# Dehyrator_TV01.net
KiCad netlist of a schematic drawn in Altium Designer
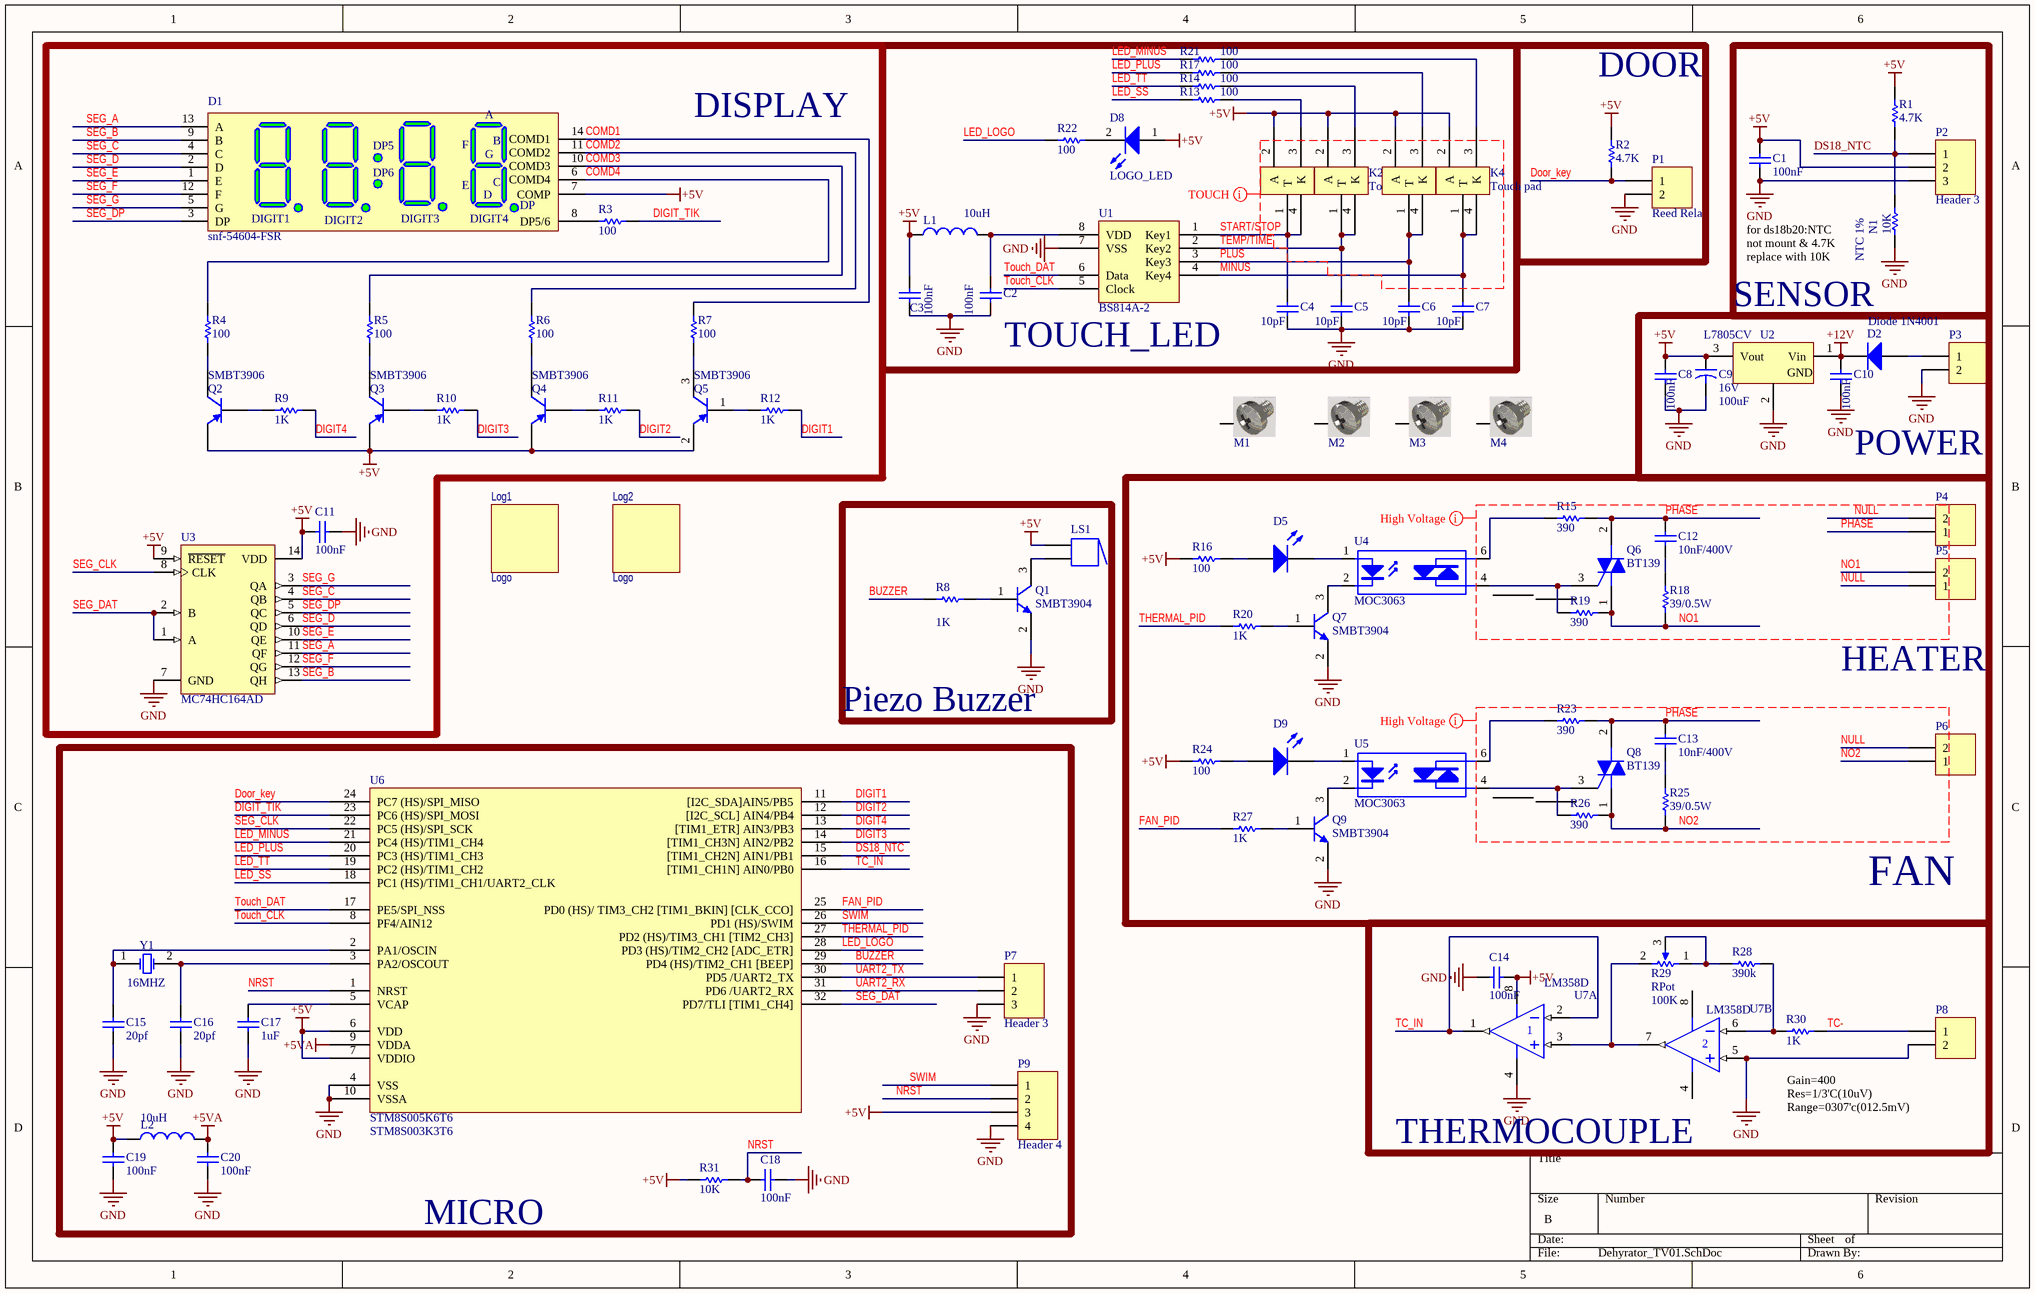
[diagram p0: Dehyrator_TV01.SchDoc]

(export (version "E")
  (design (tool "Eeschema 10.0.6"))
  (components
    (comp (ref "C1")
      (value "100nF")
      (footprint "CAP0805")
      (description "Capacitor")
      (fields (field (name "Comment") "Cap") (field (name "PUBLISHER") "Altium Limited"))
      (libsource (lib "Miscellaneous Devices") (part "Cap"))
    )
    (comp (ref "C2")
      (value "100nF")
      (footprint "CAP0805")
      (description "Capacitor")
      (fields (field (name "Comment") "Cap") (field (name "PUBLISHER") "Altium Limited"))
      (libsource (lib "Miscellaneous Devices") (part "Cap"))
    )
    (comp (ref "C3")
      (value "100nF")
      (footprint "CAP0805")
      (description "Capacitor")
      (fields (field (name "Comment") "Cap") (field (name "PUBLISHER") "Altium Limited"))
      (libsource (lib "Miscellaneous Devices") (part "Cap"))
    )
    (comp (ref "C4")
      (value "10pF")
      (footprint "CAP0805")
      (description "Capacitor")
      (fields (field (name "Comment") "Cap") (field (name "PUBLISHER") "Altium Limited"))
      (libsource (lib "Miscellaneous Devices") (part "Cap"))
    )
    (comp (ref "C5")
      (value "10pF")
      (footprint "CAP0805")
      (description "Capacitor")
      (fields (field (name "Comment") "Cap") (field (name "PUBLISHER") "Altium Limited"))
      (libsource (lib "Miscellaneous Devices") (part "Cap"))
    )
    (comp (ref "C6")
      (value "10pF")
      (footprint "CAP0805")
      (description "Capacitor")
      (fields (field (name "Comment") "Cap") (field (name "PUBLISHER") "Altium Limited"))
      (libsource (lib "Miscellaneous Devices") (part "Cap"))
    )
    (comp (ref "C7")
      (value "10pF")
      (footprint "CAP0805")
      (description "Capacitor")
      (fields (field (name "Comment") "Cap") (field (name "PUBLISHER") "Altium Limited"))
      (libsource (lib "Miscellaneous Devices") (part "Cap"))
    )
    (comp (ref "C8")
      (value "100nF")
      (footprint "CAP0805")
      (description "Capacitor")
      (fields (field (name "Comment") "Cap") (field (name "PUBLISHER") "Altium Limited"))
      (libsource (lib "Miscellaneous Devices") (part "Cap"))
    )
    (comp (ref "C9")
      (value "16V")
      (footprint "Cap electrolitic radial 5x11-2")
      (description "Capacitor")
      (fields (field (name "ALTIUM_VALUE") "100uF") (field (name "PUBLISHER") "Altium Limited"))
      (libsource (lib "Miscellaneous Devices") (part "Cap2"))
    )
    (comp (ref "C10")
      (value "100nF")
      (footprint "CAP0805")
      (description "Capacitor")
      (fields (field (name "Comment") "Cap") (field (name "PUBLISHER") "Altium Limited"))
      (libsource (lib "Miscellaneous Devices") (part "Cap"))
    )
    (comp (ref "C11")
      (value "100nF")
      (footprint "CAP0805")
      (description "Capacitor")
      (fields (field (name "Comment") "Cap") (field (name "PUBLISHER") "Altium Limited"))
      (libsource (lib "Miscellaneous Devices") (part "Cap"))
    )
    (comp (ref "C12")
      (value "10nF/400V")
      (footprint "Cap_polyester_400V")
      (description "Capacitor")
      (fields (field (name "PUBLISHER") "Altium Limited"))
      (libsource (lib "Miscellaneous Devices") (part "Cap"))
    )
    (comp (ref "C13")
      (value "10nF/400V")
      (footprint "Cap_polyester_400V")
      (description "Capacitor")
      (fields (field (name "PUBLISHER") "Altium Limited"))
      (libsource (lib "Miscellaneous Devices") (part "Cap"))
    )
    (comp (ref "C14")
      (value "100nF")
      (footprint "CAP0805")
      (description "Capacitor")
      (fields (field (name "Comment") "Cap") (field (name "PUBLISHER") "Altium Limited"))
      (libsource (lib "Miscellaneous Devices") (part "Cap"))
    )
    (comp (ref "C15")
      (value "20pf")
      (footprint "CAP0805")
      (description "Capacitor")
      (fields (field (name "Comment") "Cap") (field (name "PUBLISHER") "Altium Limited"))
      (libsource (lib "Miscellaneous Devices") (part "Cap"))
    )
    (comp (ref "C16")
      (value "20pf")
      (footprint "CAP0805")
      (description "Capacitor")
      (fields (field (name "Comment") "Cap") (field (name "PUBLISHER") "Altium Limited"))
      (libsource (lib "Miscellaneous Devices") (part "Cap"))
    )
    (comp (ref "C17")
      (value "1uF")
      (footprint "CAP0805")
      (description "Capacitor")
      (fields (field (name "Comment") "Cap") (field (name "PUBLISHER") "Altium Limited"))
      (libsource (lib "Miscellaneous Devices") (part "Cap"))
    )
    (comp (ref "C18")
      (value "100nF")
      (footprint "CAP0805")
      (description "Capacitor")
      (fields (field (name "Comment") "Cap") (field (name "PUBLISHER") "Altium Limited"))
      (libsource (lib "Miscellaneous Devices") (part "Cap"))
    )
    (comp (ref "C19")
      (value "100nF")
      (footprint "CAP0805")
      (description "Capacitor")
      (fields (field (name "Comment") "Cap") (field (name "PUBLISHER") "Altium Limited"))
      (libsource (lib "Miscellaneous Devices") (part "Cap"))
    )
    (comp (ref "C20")
      (value "100nF")
      (footprint "CAP0805")
      (description "Capacitor")
      (fields (field (name "Comment") "Cap") (field (name "PUBLISHER") "Altium Limited"))
      (libsource (lib "Miscellaneous Devices") (part "Cap"))
    )
    (comp (ref "D1")
      (value "snf-54604-FSR")
      (footprint "7SEG-4CLOCK-50x19")
      (description "4-Digit LED Display CLOCK")
      (libsource (lib "Mofidi3D") (part "7SEG-CLOCK-14PIN"))
    )
    (comp (ref "D2")
      (value "Diode 1N4001")
      (footprint "DO-241AC")
      (description "1 Amp General Purpose Rectifier")
      (fields (field (name "PUBLISHER") "Altium Limited"))
      (libsource (lib "Miscellaneous Devices") (part "Diode 1N4001"))
    )
    (comp (ref "D5")
      (value "LED1")
      (footprint "LED_0805")
      (description "Typical RED GaAs LED")
      (fields (field (name "PUBLISHER") "Altium Limited"))
      (libsource (lib "Miscellaneous Devices") (part "LED1"))
    )
    (comp (ref "D8")
      (value "LOGO_LED")
      (footprint "LED5MM_BLUE")
      (description "Typical INFRARED GaAs LED")
      (fields (field (name "PUBLISHER") "Altium Limited"))
      (libsource (lib "Miscellaneous Devices") (part "LED0"))
    )
    (comp (ref "D9")
      (value "LED1")
      (footprint "LED_0805")
      (description "Typical RED GaAs LED")
      (fields (field (name "PUBLISHER") "Altium Limited"))
      (libsource (lib "Miscellaneous Devices") (part "LED1"))
    )
    (comp (ref "K1")
      (value "Touch pad")
      (footprint "Touchled_Circular")
      (description "Capacitive touch")
      (libsource (lib "Mofidi3D") (part "Touch_Pad"))
    )
    (comp (ref "K2")
      (value "Touch pad")
      (footprint "Touchled_Circular")
      (description "Capacitive touch")
      (libsource (lib "Mofidi3D") (part "Touch_Pad"))
    )
    (comp (ref "K3")
      (value "Touch pad")
      (footprint "Touchled_Circular")
      (description "Capacitive touch")
      (libsource (lib "Mofidi3D") (part "Touch_Pad"))
    )
    (comp (ref "K4")
      (value "Touch pad")
      (footprint "Touchled_Circular")
      (description "Capacitive touch")
      (libsource (lib "Mofidi3D") (part "Touch_Pad"))
    )
    (comp (ref "L1")
      (value "10uH")
      (footprint "IND0805")
      (description "Inductor")
      (fields (field (name "PUBLISHER") "Altium Limited"))
      (libsource (lib "Miscellaneous Devices") (part "Inductor"))
    )
    (comp (ref "L2")
      (value "10uH")
      (footprint "IND0805")
      (description "Inductor")
      (fields (field (name "PUBLISHER") "Altium Limited"))
      (libsource (lib "Miscellaneous Devices") (part "Inductor"))
    )
    (comp (ref "Log1") (value "Logo") (footprint "LOGO_PARS_TOP") (libsource (lib "Mofidi3D") (part "Logo")))
    (comp (ref "Log2") (value "Logo") (footprint "LOGO_PARS_TOP") (libsource (lib "Mofidi3D") (part "Logo")))
    (comp (ref "LS1")
      (value "Buzzer")
      (footprint "BUZZER_12A05")
      (description "Magnetic Transducer Buzzer")
      (fields (field (name "PUBLISHER") "Altium Limited"))
      (libsource (lib "Miscellaneous Devices") (part "Buzzer"))
    )
    (comp (ref "M1")
      (value "Screw3mm")
      (footprint "Board Screw 3mm")
      (description "Board Screw With Spacer 3mm")
      (fields (field (name "DESIGNER") "Abbas Basereh"))
      (libsource (lib "Mofidi3D") (part "Board Screw 3mm"))
    )
    (comp (ref "M2")
      (value "Screw3mm")
      (footprint "Board Screw 3mm")
      (description "Board Screw With Spacer 3mm")
      (fields (field (name "DESIGNER") "Abbas Basereh"))
      (libsource (lib "Mofidi3D") (part "Board Screw 3mm"))
    )
    (comp (ref "M3")
      (value "Screw3mm")
      (footprint "Board Screw 3mm")
      (description "Board Screw With Spacer 3mm")
      (fields (field (name "DESIGNER") "Abbas Basereh"))
      (libsource (lib "Mofidi3D") (part "Board Screw 3mm"))
    )
    (comp (ref "M4")
      (value "Screw3mm")
      (footprint "Board Screw 3mm")
      (description "Board Screw With Spacer 3mm")
      (fields (field (name "DESIGNER") "Abbas Basereh"))
      (libsource (lib "Mofidi3D") (part "Board Screw 3mm"))
    )
    (comp (ref "N1")
      (value "NTC 1%")
      (footprint "Axial 0_25 W, 0_4 IN LEAD PITCH")
      (description "Resistor")
      (fields (field (name "ALTIUM_VALUE") "10K") (field (name "PUBLISHER") "Altium Limited"))
      (libsource (lib "Miscellaneous Devices") (part "Res1"))
    )
    (comp (ref "P1")
      (value "Reed Relay")
      (footprint "DS1070-2-COMCON")
      (description "Header, 2-Pin")
      (fields (field (name "PUBLISHER") "Altium Limited"))
      (libsource (lib "Miscellaneous Connectors") (part "Header 2"))
    )
    (comp (ref "P2")
      (value "Header 3")
      (footprint "XH-3PIN")
      (description "Header, 3-Pin")
      (fields (field (name "PUBLISHER") "Altium Limited"))
      (libsource (lib "Miscellaneous Connectors") (part "Header 3"))
    )
    (comp (ref "P3")
      (value "Header 2")
      (footprint "KF301 2PIN")
      (description "Header, 2-Pin")
      (fields (field (name "PUBLISHER") "Altium Limited"))
      (libsource (lib "Miscellaneous Connectors") (part "Header 2"))
    )
    (comp (ref "P4")
      (value "Header 2")
      (footprint "KF301 2PIN")
      (description "Header, 2-Pin")
      (fields (field (name "PUBLISHER") "Altium Limited"))
      (libsource (lib "") (part "Header 2_1"))
    )
    (comp (ref "P5")
      (value "Header 2")
      (footprint "KF301 2PIN")
      (description "Header, 2-Pin")
      (fields (field (name "PUBLISHER") "Altium Limited"))
      (libsource (lib "") (part "Header 2_1"))
    )
    (comp (ref "P6")
      (value "Header 2")
      (footprint "KF301 2PIN")
      (description "Header, 2-Pin")
      (fields (field (name "PUBLISHER") "Altium Limited"))
      (libsource (lib "") (part "Header 2_1"))
    )
    (comp (ref "P7")
      (value "Header 3")
      (footprint "PIN_M_1x3")
      (description "Header, 3-Pin")
      (fields (field (name "PUBLISHER") "Altium Limited"))
      (libsource (lib "Miscellaneous Connectors") (part "Header 3"))
    )
    (comp (ref "P8")
      (value "Header 2")
      (footprint "KF35C 2PIN")
      (description "Header, 2-Pin")
      (fields (field (name "PUBLISHER") "Altium Limited"))
      (libsource (lib "Miscellaneous Connectors") (part "Header 2"))
    )
    (comp (ref "P9")
      (value "Header 4")
      (footprint "HDR_1x4")
      (description "Header, 4-Pin")
      (fields (field (name "PUBLISHER") "Altium Limited"))
      (libsource (lib "Miscellaneous Connectors") (part "Header 4"))
    )
    (comp (ref "Q1")
      (value "SMBT3904")
      (footprint "SOT23_N")
      (description "NPN Silicon Switching Transistor, 40 V VCEO, 200 mA IC, SOT23, Reel, Green")
      (fields (field (name "MANUFACTURER") "Infineon"))
      (libsource (lib "Infineon Transistor & Diode") (part "SMBT3904"))
    )
    (comp (ref "Q2")
      (value "SMBT3906")
      (footprint "SOT23_N")
      (description "PNP Silicon Switching Transistor, 40 V VCEO, 200 mA IC, SOT23, Reel, Green")
      (fields (field (name "MANUFACTURER") "Infineon"))
      (libsource (lib "Infineon Transistor & Diode") (part "SMBT3906"))
    )
    (comp (ref "Q3")
      (value "SMBT3906")
      (footprint "SOT23_N")
      (description "PNP Silicon Switching Transistor, 40 V VCEO, 200 mA IC, SOT23, Reel, Green")
      (fields (field (name "MANUFACTURER") "Infineon"))
      (libsource (lib "Infineon Transistor & Diode") (part "SMBT3906"))
    )
    (comp (ref "Q4")
      (value "SMBT3906")
      (footprint "SOT23_N")
      (description "PNP Silicon Switching Transistor, 40 V VCEO, 200 mA IC, SOT23, Reel, Green")
      (fields (field (name "MANUFACTURER") "Infineon"))
      (libsource (lib "Infineon Transistor & Diode") (part "SMBT3906"))
    )
    (comp (ref "Q5")
      (value "SMBT3906")
      (footprint "SOT23_N")
      (description "PNP Silicon Switching Transistor, 40 V VCEO, 200 mA IC, SOT23, Reel, Green")
      (fields (field (name "MANUFACTURER") "Infineon"))
      (libsource (lib "") (part "SMBT3906_1"))
    )
    (comp (ref "Q6")
      (value "BT139")
      (footprint "TO-220 AB WITH HEAT SINK")
      (description "Silicon Bidirectional Triode Thyristor")
      (fields (field (name "PUBLISHER") "Altium Limited"))
      (libsource (lib "Miscellaneous Devices") (part "Triac"))
    )
    (comp (ref "Q7")
      (value "SMBT3904")
      (footprint "SOT23_N")
      (description "NPN Silicon Switching Transistor, 40 V VCEO, 200 mA IC, SOT23, Reel, Green")
      (fields (field (name "MANUFACTURER") "Infineon"))
      (libsource (lib "Infineon Transistor & Diode") (part "SMBT3904"))
    )
    (comp (ref "Q8")
      (value "BT139")
      (footprint "TO-220 AB WITH HEAT SINK")
      (description "Silicon Bidirectional Triode Thyristor")
      (fields (field (name "PUBLISHER") "Altium Limited"))
      (libsource (lib "Miscellaneous Devices") (part "Triac"))
    )
    (comp (ref "Q9")
      (value "SMBT3904")
      (footprint "SOT23_N")
      (description "NPN Silicon Switching Transistor, 40 V VCEO, 200 mA IC, SOT23, Reel, Green")
      (fields (field (name "MANUFACTURER") "Infineon"))
      (libsource (lib "Infineon Transistor & Diode") (part "SMBT3904"))
    )
    (comp (ref "R1")
      (value "4.7K")
      (footprint "RES0805")
      (description "Resistor")
      (fields (field (name "Comment") "Res1") (field (name "PUBLISHER") "Altium Limited"))
      (libsource (lib "Miscellaneous Devices") (part "Res1"))
    )
    (comp (ref "R2")
      (value "4.7K")
      (footprint "RES0805")
      (description "Resistor")
      (fields (field (name "Comment") "Res1") (field (name "PUBLISHER") "Altium Limited"))
      (libsource (lib "Miscellaneous Devices") (part "Res1"))
    )
    (comp (ref "R3")
      (value "100")
      (footprint "RES0805")
      (description "Resistor")
      (fields (field (name "Comment") "Res1") (field (name "PUBLISHER") "Altium Limited"))
      (libsource (lib "Miscellaneous Devices") (part "Res1"))
    )
    (comp (ref "R4")
      (value "100")
      (footprint "RES0805")
      (description "Resistor")
      (fields (field (name "Comment") "Res1") (field (name "PUBLISHER") "Altium Limited"))
      (libsource (lib "Miscellaneous Devices") (part "Res1"))
    )
    (comp (ref "R5")
      (value "100")
      (footprint "RES0805")
      (description "Resistor")
      (fields (field (name "Comment") "Res1") (field (name "PUBLISHER") "Altium Limited"))
      (libsource (lib "Miscellaneous Devices") (part "Res1"))
    )
    (comp (ref "R6")
      (value "100")
      (footprint "RES0805")
      (description "Resistor")
      (fields (field (name "Comment") "Res1") (field (name "PUBLISHER") "Altium Limited"))
      (libsource (lib "Miscellaneous Devices") (part "Res1"))
    )
    (comp (ref "R7")
      (value "100")
      (footprint "RES0805")
      (description "Resistor")
      (fields (field (name "Comment") "Res1") (field (name "PUBLISHER") "Altium Limited"))
      (libsource (lib "Miscellaneous Devices") (part "Res1"))
    )
    (comp (ref "R8")
      (value "1K")
      (footprint "RES0805")
      (description "Resistor")
      (fields (field (name "Comment") "Res1") (field (name "PUBLISHER") "Altium Limited"))
      (libsource (lib "Miscellaneous Devices") (part "Res1"))
    )
    (comp (ref "R9")
      (value "1K")
      (footprint "RES0805")
      (description "Resistor")
      (fields (field (name "Comment") "Res1") (field (name "PUBLISHER") "Altium Limited"))
      (libsource (lib "Miscellaneous Devices") (part "Res1"))
    )
    (comp (ref "R10")
      (value "1K")
      (footprint "RES0805")
      (description "Resistor")
      (fields (field (name "Comment") "Res1") (field (name "PUBLISHER") "Altium Limited"))
      (libsource (lib "Miscellaneous Devices") (part "Res1"))
    )
    (comp (ref "R11")
      (value "1K")
      (footprint "RES0805")
      (description "Resistor")
      (fields (field (name "Comment") "Res1") (field (name "PUBLISHER") "Altium Limited"))
      (libsource (lib "Miscellaneous Devices") (part "Res1"))
    )
    (comp (ref "R12")
      (value "1K")
      (footprint "RES0805")
      (description "Resistor")
      (fields (field (name "Comment") "Res1") (field (name "PUBLISHER") "Altium Limited"))
      (libsource (lib "Miscellaneous Devices") (part "Res1"))
    )
    (comp (ref "R13")
      (value "100")
      (footprint "RES0805")
      (description "Resistor")
      (fields (field (name "Comment") "Res1") (field (name "PUBLISHER") "Altium Limited"))
      (libsource (lib "Miscellaneous Devices") (part "Res1"))
    )
    (comp (ref "R14")
      (value "100")
      (footprint "RES0805")
      (description "Resistor")
      (fields (field (name "Comment") "Res1") (field (name "PUBLISHER") "Altium Limited"))
      (libsource (lib "Miscellaneous Devices") (part "Res1"))
    )
    (comp (ref "R15")
      (value "390")
      (footprint "Axial 0_5W 5_0mm")
      (description "Resistor")
      (fields (field (name "Comment") "Res1") (field (name "PUBLISHER") "Altium Limited"))
      (libsource (lib "Miscellaneous Devices") (part "Res1"))
    )
    (comp (ref "R16")
      (value "100")
      (footprint "RES0805")
      (description "Resistor")
      (fields (field (name "Comment") "Res1") (field (name "PUBLISHER") "Altium Limited"))
      (libsource (lib "Miscellaneous Devices") (part "Res1"))
    )
    (comp (ref "R17")
      (value "100")
      (footprint "RES0805")
      (description "Resistor")
      (fields (field (name "Comment") "Res1") (field (name "PUBLISHER") "Altium Limited"))
      (libsource (lib "Miscellaneous Devices") (part "Res1"))
    )
    (comp (ref "R18")
      (value "39/0.5W")
      (footprint "Axial 1W  7_0mm")
      (description "Resistor")
      (fields (field (name "Comment") "Res1") (field (name "PUBLISHER") "Altium Limited"))
      (libsource (lib "Miscellaneous Devices") (part "Res1"))
    )
    (comp (ref "R19")
      (value "390")
      (footprint "Axial 0_5W 5_0mm")
      (description "Resistor")
      (fields (field (name "Comment") "Res1") (field (name "PUBLISHER") "Altium Limited"))
      (libsource (lib "Miscellaneous Devices") (part "Res1"))
    )
    (comp (ref "R20")
      (value "1K")
      (footprint "RES0805")
      (description "Resistor")
      (fields (field (name "Comment") "Res1") (field (name "PUBLISHER") "Altium Limited"))
      (libsource (lib "Miscellaneous Devices") (part "Res1"))
    )
    (comp (ref "R21")
      (value "100")
      (footprint "RES0805")
      (description "Resistor")
      (fields (field (name "Comment") "Res1") (field (name "PUBLISHER") "Altium Limited"))
      (libsource (lib "Miscellaneous Devices") (part "Res1"))
    )
    (comp (ref "R22")
      (value "100")
      (footprint "RES0805")
      (description "Resistor")
      (fields (field (name "Comment") "Res1") (field (name "PUBLISHER") "Altium Limited"))
      (libsource (lib "Miscellaneous Devices") (part "Res1"))
    )
    (comp (ref "R23")
      (value "390")
      (footprint "Axial 0_5W 5_0mm")
      (description "Resistor")
      (fields (field (name "Comment") "Res1") (field (name "PUBLISHER") "Altium Limited"))
      (libsource (lib "Miscellaneous Devices") (part "Res1"))
    )
    (comp (ref "R24")
      (value "100")
      (footprint "RES0805")
      (description "Resistor")
      (fields (field (name "Comment") "Res1") (field (name "PUBLISHER") "Altium Limited"))
      (libsource (lib "Miscellaneous Devices") (part "Res1"))
    )
    (comp (ref "R25")
      (value "39/0.5W")
      (footprint "Axial 1W  7_0mm")
      (description "Resistor")
      (fields (field (name "Comment") "Res1") (field (name "PUBLISHER") "Altium Limited"))
      (libsource (lib "Miscellaneous Devices") (part "Res1"))
    )
    (comp (ref "R26")
      (value "390")
      (footprint "Axial 0_5W 5_0mm")
      (description "Resistor")
      (fields (field (name "Comment") "Res1") (field (name "PUBLISHER") "Altium Limited"))
      (libsource (lib "Miscellaneous Devices") (part "Res1"))
    )
    (comp (ref "R27")
      (value "1K")
      (footprint "RES0805")
      (description "Resistor")
      (fields (field (name "Comment") "Res1") (field (name "PUBLISHER") "Altium Limited"))
      (libsource (lib "Miscellaneous Devices") (part "Res1"))
    )
    (comp (ref "R28")
      (value "390k")
      (footprint "RES0805")
      (description "Resistor")
      (fields (field (name "Comment") "Res1") (field (name "PUBLISHER") "Altium Limited"))
      (libsource (lib "Miscellaneous Devices") (part "Res1"))
    )
    (comp (ref "R29")
      (value "RPot")
      (footprint "Potentiometer_4mm_3364A_smd")
      (description "Potentiometer")
      (fields (field (name "ALTIUM_VALUE") "100K") (field (name "PUBLISHER") "Altium Limited"))
      (libsource (lib "Miscellaneous Devices") (part "RPot"))
    )
    (comp (ref "R30")
      (value "1K")
      (footprint "RES0805")
      (description "Resistor")
      (fields (field (name "Comment") "Res1") (field (name "PUBLISHER") "Altium Limited"))
      (libsource (lib "Miscellaneous Devices") (part "Res1"))
    )
    (comp (ref "R31")
      (value "10K")
      (footprint "RES0805")
      (description "Resistor")
      (fields (field (name "Comment") "Res1") (field (name "PUBLISHER") "Altium Limited"))
      (libsource (lib "Miscellaneous Devices") (part "Res1"))
    )
    (comp (ref "U1")
      (value "BS814A-2")
      (footprint "SO-8N")
      (description "Holtek Touch Key")
      (libsource (lib "Mofidi3D") (part "BS814A-2"))
    )
    (comp (ref "U2")
      (value "L7805CV")
      (footprint "TO-220 AB WITH HEAT SINK")
      (description "Linear Voltage Regulator IC Positive FIXED")
      (fields (field (name "MANUFACTURER") "STMicroelectronics") (field (name "DESIGNER") "Abbas Basereh"))
      (libsource (lib "Mofidi3D") (part "L7805CV-Linear Voltage Regulator IC Positive 1 Output 5V 1.5A TO-220AB"))
    )
    (comp (ref "U3")
      (value "MC74HC164AD")
      (footprint "SO14_N")
      (description "8-Bit Serial Input / Parallel-Output Shift Register")
      (fields (field (name "PUBLISHER") "Altium Limited"))
      (libsource (lib "ON Semi Logic Register") (part "MC74HC164AD"))
    )
    (comp (ref "U4")
      (value "MOC3063")
      (footprint "MOC3063")
      (description "Opto-Triac")
      (fields (field (name "PUBLISHER") "Altium Limited"))
      (libsource (lib "Miscellaneous Devices") (part "Opto TRIAC"))
    )
    (comp (ref "U5")
      (value "MOC3063")
      (footprint "MOC3063")
      (description "Opto-Triac")
      (fields (field (name "PUBLISHER") "Altium Limited"))
      (libsource (lib "Miscellaneous Devices") (part "Opto TRIAC"))
    )
    (comp (ref "U6")
      (value "STM8S005K6T6")
      (footprint "LQFP32_N")
      (libsource (lib "Mofidi3D") (part "STM8S005K6T6"))
    )
    (comp (ref "U7")
      (value "LM358D")
      (footprint "SO-8N")
      (description "Dual Low-Power Operational Amplifier")
      (fields (field (name "PUBLISHER") "Altium Limited"))
      (libsource (lib "Motorola Amplifier Operational Amplifier") (part "LM358D"))
    )
    (comp (ref "Y1")
      (value "16MHZ")
      (footprint "CRYSTAL Small")
      (description "Crystal Oscillator")
      (fields (field (name "PUBLISHER") "Altium Limited"))
      (libsource (lib "ECS Crystal Oscillator") (part "ECS-110-S-5P"))
    )
  )
  (nets
    (net (code "1") (name "+5V") (class "Default")
      (node (ref "C1") (pin "2") (pinfunction "2_2") (pintype "passive"))
      (node (ref "C11") (pin "2") (pinfunction "2_2") (pintype "passive"))
      (node (ref "C14") (pin "1") (pinfunction "1_1") (pintype "passive"))
      (node (ref "C19") (pin "2") (pinfunction "2_2") (pintype "passive"))
      (node (ref "C3") (pin "2") (pinfunction "2_2") (pintype "passive"))
      (node (ref "C8") (pin "2") (pinfunction "2_2") (pintype "passive"))
      (node (ref "C9") (pin "1") (pinfunction "1_1") (pintype "passive"))
      (node (ref "D1") (pin "7") (pinfunction "COMP_7") (pintype "passive"))
      (node (ref "D8") (pin "1") (pinfunction "A_1") (pintype "passive"))
      (node (ref "K1") (pin "2") (pinfunction "A_2") (pintype "passive"))
      (node (ref "K2") (pin "2") (pinfunction "A_2") (pintype "passive"))
      (node (ref "K3") (pin "2") (pinfunction "A_2") (pintype "passive"))
      (node (ref "K4") (pin "2") (pinfunction "A_2") (pintype "passive"))
      (node (ref "L1") (pin "1") (pinfunction "1_1") (pintype "passive"))
      (node (ref "L2") (pin "1") (pinfunction "1_1") (pintype "passive"))
      (node (ref "LS1") (pin "1") (pinfunction "1_1") (pintype "passive"))
      (node (ref "P2") (pin "2") (pinfunction "2_2") (pintype "passive"))
      (node (ref "P9") (pin "3") (pinfunction "3_3") (pintype "passive"))
      (node (ref "Q2") (pin "2") (pinfunction "E_2") (pintype "passive"))
      (node (ref "Q3") (pin "2") (pinfunction "E_2") (pintype "passive"))
      (node (ref "Q4") (pin "2") (pinfunction "E_2") (pintype "passive"))
      (node (ref "Q5") (pin "2") (pinfunction "E_2") (pintype "passive"))
      (node (ref "R1") (pin "2") (pinfunction "2_2") (pintype "passive"))
      (node (ref "R16") (pin "1") (pinfunction "1_1") (pintype "passive"))
      (node (ref "R2") (pin "2") (pinfunction "2_2") (pintype "passive"))
      (node (ref "R24") (pin "1") (pinfunction "1_1") (pintype "passive"))
      (node (ref "R31") (pin "1") (pinfunction "1_1") (pintype "passive"))
      (node (ref "U2") (pin "3") (pinfunction "Vout_3") (pintype "passive"))
      (node (ref "U3") (pin "14") (pinfunction "VDD_14") (pintype "power_in"))
      (node (ref "U3") (pin "9") (pinfunction "~{RESET}_9") (pintype "input"))
      (node (ref "U6") (pin "6") (pinfunction "VDD_6") (pintype "passive"))
      (node (ref "U6") (pin "7") (pinfunction "VDDIO_7") (pintype "passive"))
      (node (ref "U7") (pin "8") (pinfunction "V+_8") (pintype "power_in"))
    )
    (net (code "2") (name "+5VA") (class "Default")
      (node (ref "C20") (pin "2") (pinfunction "2_2") (pintype "passive"))
      (node (ref "L2") (pin "2") (pinfunction "2_2") (pintype "passive"))
      (node (ref "U6") (pin "9") (pinfunction "VDDA_9") (pintype "passive"))
    )
    (net (code "3") (name "+12V") (class "Default")
      (node (ref "C10") (pin "2") (pinfunction "2_2") (pintype "passive"))
      (node (ref "D2") (pin "2") (pinfunction "K_2") (pintype "passive"))
      (node (ref "U2") (pin "1") (pinfunction "Vin_1") (pintype "passive"))
    )
    (net (code "4") (name "/BUZZER") (class "Default")
      (node (ref "R8") (pin "1") (pinfunction "1_1") (pintype "passive"))
      (node (ref "U6") (pin "29") (pinfunction "PD4_(HS)/TIM2_CH1_[BEEP]_29") (pintype "passive"))
    )
    (net (code "5") (name "/COMD1") (class "Default")
      (node (ref "D1") (pin "14") (pinfunction "COMD1_14") (pintype "passive"))
      (node (ref "R7") (pin "2") (pinfunction "2_2") (pintype "passive"))
    )
    (net (code "6") (name "/COMD2") (class "Default")
      (node (ref "D1") (pin "11") (pinfunction "COMD2_11") (pintype "passive"))
      (node (ref "R6") (pin "2") (pinfunction "2_2") (pintype "passive"))
    )
    (net (code "7") (name "/COMD3") (class "Default")
      (node (ref "D1") (pin "10") (pinfunction "COMD3_10") (pintype "passive"))
      (node (ref "R5") (pin "2") (pinfunction "2_2") (pintype "passive"))
    )
    (net (code "8") (name "/COMD4") (class "Default")
      (node (ref "D1") (pin "6") (pinfunction "COMD4_6") (pintype "passive"))
      (node (ref "R4") (pin "2") (pinfunction "2_2") (pintype "passive"))
    )
    (net (code "9") (name "/DIGIT1") (class "Default")
      (node (ref "R12") (pin "2") (pinfunction "2_2") (pintype "passive"))
      (node (ref "U6") (pin "11") (pinfunction "[I2C_SDA]AIN5/PB5_11") (pintype "passive"))
    )
    (net (code "10") (name "/DIGIT2") (class "Default")
      (node (ref "R11") (pin "2") (pinfunction "2_2") (pintype "passive"))
      (node (ref "U6") (pin "12") (pinfunction "[I2C_SCL]_AIN4/PB4_12") (pintype "passive"))
    )
    (net (code "11") (name "/DIGIT3") (class "Default")
      (node (ref "R10") (pin "2") (pinfunction "2_2") (pintype "passive"))
      (node (ref "U6") (pin "14") (pinfunction "[TIM1_CH3N]_AIN2/PB2_14") (pintype "passive"))
    )
    (net (code "12") (name "/DIGIT4") (class "Default")
      (node (ref "R9") (pin "2") (pinfunction "2_2") (pintype "passive"))
      (node (ref "U6") (pin "13") (pinfunction "[TIM1_ETR]_AIN3/PB3_13") (pintype "passive"))
    )
    (net (code "13") (name "/DIGIT_TIK") (class "Default")
      (node (ref "R3") (pin "2") (pinfunction "2_2") (pintype "passive"))
      (node (ref "U6") (pin "23") (pinfunction "PC6_(HS)/SPI_MOSI_23") (pintype "passive"))
    )
    (net (code "14") (name "/DS18_NTC") (class "Default")
      (node (ref "N1") (pin "1") (pinfunction "1_1") (pintype "passive"))
      (node (ref "P2") (pin "1") (pinfunction "1_1") (pintype "passive"))
      (node (ref "R1") (pin "1") (pinfunction "1_1") (pintype "passive"))
      (node (ref "U6") (pin "15") (pinfunction "[TIM1_CH2N]_AIN1/PB1_15") (pintype "passive"))
    )
    (net (code "15") (name "/Door_key") (class "Default")
      (node (ref "P1") (pin "1") (pinfunction "1_1") (pintype "passive"))
      (node (ref "R2") (pin "1") (pinfunction "1_1") (pintype "passive"))
      (node (ref "U6") (pin "24") (pinfunction "PC7_(HS)/SPI_MISO_24") (pintype "passive"))
    )
    (net (code "16") (name "/FAN_PID") (class "Default")
      (node (ref "R27") (pin "1") (pinfunction "1_1") (pintype "passive"))
      (node (ref "U6") (pin "25") (pinfunction "PD0_(HS)/_TIM3_CH2_[TIM1_BKIN]_[CLK_CCO]_25") (pintype "passive"))
    )
    (net (code "17") (name "/LED_LOGO") (class "Default")
      (node (ref "R22") (pin "1") (pinfunction "1_1") (pintype "passive"))
      (node (ref "U6") (pin "28") (pinfunction "PD3_(HS)/TIM2_CH2_[ADC_ETR]_28") (pintype "passive"))
    )
    (net (code "18") (name "/LED_MINUS") (class "Default")
      (node (ref "R21") (pin "1") (pinfunction "1_1") (pintype "passive"))
      (node (ref "U6") (pin "21") (pinfunction "PC4_(HS)/TIM1_CH4_21") (pintype "passive"))
    )
    (net (code "19") (name "/LED_PLUS") (class "Default")
      (node (ref "R17") (pin "1") (pinfunction "1_1") (pintype "passive"))
      (node (ref "U6") (pin "20") (pinfunction "PC3_(HS)/TIM1_CH3_20") (pintype "passive"))
    )
    (net (code "20") (name "/LED_SS") (class "Default")
      (node (ref "R13") (pin "1") (pinfunction "1_1") (pintype "passive"))
      (node (ref "U6") (pin "18") (pinfunction "PC1_(HS)/TIM1_CH1/UART2_CLK_18") (pintype "passive"))
    )
    (net (code "21") (name "/LED_TT") (class "Default")
      (node (ref "R14") (pin "1") (pinfunction "1_1") (pintype "passive"))
      (node (ref "U6") (pin "19") (pinfunction "PC2_(HS)/TIM1_CH2_19") (pintype "passive"))
    )
    (net (code "22") (name "/MINUS") (class "Default")
      (node (ref "C7") (pin "2") (pinfunction "2_2") (pintype "passive"))
      (node (ref "K4") (pin "1") (pinfunction "T_1") (pintype "passive"))
      (node (ref "K4") (pin "4") (pintype "passive"))
      (node (ref "U1") (pin "4") (pinfunction "Key4_4") (pintype "passive"))
    )
    (net (code "23") (name "/NO1") (class "Default")
      (node (ref "P5") (pin "2") (pinfunction "2_2") (pintype "passive"))
      (node (ref "Q6") (pin "1") (pinfunction "M1_1") (pintype "passive"))
      (node (ref "R18") (pin "1") (pinfunction "1_1") (pintype "passive"))
      (node (ref "R19") (pin "1") (pinfunction "1_1") (pintype "passive"))
    )
    (net (code "24") (name "/NO2") (class "Default")
      (node (ref "P6") (pin "1") (pinfunction "1_1") (pintype "passive"))
      (node (ref "Q8") (pin "1") (pinfunction "M1_1") (pintype "passive"))
      (node (ref "R25") (pin "1") (pinfunction "1_1") (pintype "passive"))
      (node (ref "R26") (pin "1") (pinfunction "1_1") (pintype "passive"))
    )
    (net (code "25") (name "/NRST") (class "Default")
      (node (ref "C18") (pin "1") (pinfunction "1_1") (pintype "passive"))
      (node (ref "P9") (pin "2") (pinfunction "2_2") (pintype "passive"))
      (node (ref "R31") (pin "2") (pinfunction "2_2") (pintype "passive"))
      (node (ref "U6") (pin "1") (pinfunction "NRST_1") (pintype "passive"))
    )
    (net (code "26") (name "/NULL") (class "Default")
      (node (ref "P4") (pin "2") (pinfunction "2_2") (pintype "passive"))
      (node (ref "P5") (pin "1") (pinfunction "1_1") (pintype "passive"))
      (node (ref "P6") (pin "2") (pinfunction "2_2") (pintype "passive"))
    )
    (net (code "27") (name "/PHASE") (class "Default")
      (node (ref "C12") (pin "1") (pinfunction "1_1") (pintype "passive"))
      (node (ref "C13") (pin "1") (pinfunction "1_1") (pintype "passive"))
      (node (ref "P4") (pin "1") (pinfunction "1_1") (pintype "passive"))
      (node (ref "Q6") (pin "2") (pinfunction "M2_2") (pintype "passive"))
      (node (ref "Q8") (pin "2") (pinfunction "M2_2") (pintype "passive"))
      (node (ref "R15") (pin "1") (pinfunction "1_1") (pintype "passive"))
      (node (ref "R23") (pin "1") (pinfunction "1_1") (pintype "passive"))
    )
    (net (code "28") (name "/PLUS") (class "Default")
      (node (ref "C6") (pin "2") (pinfunction "2_2") (pintype "passive"))
      (node (ref "K3") (pin "1") (pinfunction "T_1") (pintype "passive"))
      (node (ref "K3") (pin "4") (pintype "passive"))
      (node (ref "U1") (pin "3") (pinfunction "Key3_3") (pintype "passive"))
    )
    (net (code "29") (name "/SEG_A") (class "Default")
      (node (ref "D1") (pin "13") (pinfunction "A_13") (pintype "passive"))
      (node (ref "U3") (pin "11") (pinfunction "QF_11") (pintype "output"))
    )
    (net (code "30") (name "/SEG_B") (class "Default")
      (node (ref "D1") (pin "9") (pinfunction "B_9") (pintype "passive"))
      (node (ref "U3") (pin "13") (pinfunction "QH_13") (pintype "output"))
    )
    (net (code "31") (name "/SEG_C") (class "Default")
      (node (ref "D1") (pin "4") (pinfunction "C_4") (pintype "passive"))
      (node (ref "U3") (pin "4") (pinfunction "QB_4") (pintype "output"))
    )
    (net (code "32") (name "/SEG_CLK") (class "Default")
      (node (ref "U3") (pin "8") (pinfunction "CLK_8") (pintype "input"))
      (node (ref "U6") (pin "22") (pinfunction "PC5_(HS)/SPI_SCK_22") (pintype "passive"))
    )
    (net (code "33") (name "/SEG_D") (class "Default")
      (node (ref "D1") (pin "2") (pinfunction "D_2") (pintype "passive"))
      (node (ref "U3") (pin "6") (pinfunction "QD_6") (pintype "output"))
    )
    (net (code "34") (name "/SEG_DAT") (class "Default")
      (node (ref "U3") (pin "1") (pinfunction "A_1") (pintype "input"))
      (node (ref "U3") (pin "2") (pinfunction "B_2") (pintype "input"))
      (node (ref "U6") (pin "32") (pinfunction "PD7/TLI_[TIM1_CH4]_32") (pintype "passive"))
    )
    (net (code "35") (name "/SEG_DP") (class "Default")
      (node (ref "D1") (pin "3") (pinfunction "DP_3") (pintype "passive"))
      (node (ref "U3") (pin "5") (pinfunction "QC_5") (pintype "output"))
    )
    (net (code "36") (name "/SEG_E") (class "Default")
      (node (ref "D1") (pin "1") (pinfunction "E_1") (pintype "passive"))
      (node (ref "U3") (pin "10") (pinfunction "QE_10") (pintype "output"))
    )
    (net (code "37") (name "/SEG_F") (class "Default")
      (node (ref "D1") (pin "12") (pinfunction "F_12") (pintype "passive"))
      (node (ref "U3") (pin "12") (pinfunction "QG_12") (pintype "output"))
    )
    (net (code "38") (name "/SEG_G") (class "Default")
      (node (ref "D1") (pin "5") (pinfunction "G_5") (pintype "passive"))
      (node (ref "U3") (pin "3") (pinfunction "QA_3") (pintype "output"))
    )
    (net (code "39") (name "/START{slash}STOP") (class "Default")
      (node (ref "C4") (pin "2") (pinfunction "2_2") (pintype "passive"))
      (node (ref "K1") (pin "1") (pinfunction "T_1") (pintype "passive"))
      (node (ref "K1") (pin "4") (pintype "passive"))
      (node (ref "U1") (pin "1") (pinfunction "Key1_1") (pintype "passive"))
    )
    (net (code "40") (name "/SWIM") (class "Default")
      (node (ref "P9") (pin "1") (pinfunction "1_1") (pintype "passive"))
      (node (ref "U6") (pin "26") (pinfunction "PD1_(HS)/SWIM_26") (pintype "passive"))
    )
    (net (code "41") (name "/TC-") (class "Default")
      (node (ref "P8") (pin "1") (pinfunction "1_1") (pintype "passive"))
      (node (ref "R30") (pin "2") (pinfunction "2_2") (pintype "passive"))
    )
    (net (code "42") (name "/TC_IN") (class "Default")
      (node (ref "U6") (pin "16") (pinfunction "[TIM1_CH1N]_AIN0/PB0_16") (pintype "passive"))
      (node (ref "U7") (pin "1") (pinfunction "OUT_1") (pintype "output"))
      (node (ref "U7") (pin "2") (pinfunction "IN-_2") (pintype "input"))
    )
    (net (code "43") (name "/TEMP{slash}TIME") (class "Default")
      (node (ref "C5") (pin "2") (pinfunction "2_2") (pintype "passive"))
      (node (ref "K2") (pin "1") (pinfunction "T_1") (pintype "passive"))
      (node (ref "K2") (pin "4") (pintype "passive"))
      (node (ref "U1") (pin "2") (pinfunction "Key2_2") (pintype "passive"))
    )
    (net (code "44") (name "/THERMAL_PID") (class "Default")
      (node (ref "R20") (pin "1") (pinfunction "1_1") (pintype "passive"))
      (node (ref "U6") (pin "27") (pinfunction "PD2_(HS)/TIM3_CH1_[TIM2_CH3]_27") (pintype "passive"))
    )
    (net (code "45") (name "/Touch_CLK") (class "Default")
      (node (ref "U1") (pin "5") (pinfunction "Clock_5") (pintype "passive"))
      (node (ref "U6") (pin "8") (pinfunction "PF4/AIN12_8") (pintype "passive"))
    )
    (net (code "46") (name "/Touch_DAT") (class "Default")
      (node (ref "U1") (pin "6") (pinfunction "Data_6") (pintype "passive"))
      (node (ref "U6") (pin "17") (pinfunction "PE5/SPI_NSS_17") (pintype "passive"))
    )
    (net (code "47") (name "/UART2_RX") (class "Default")
      (node (ref "P7") (pin "2") (pinfunction "2_2") (pintype "passive"))
      (node (ref "U6") (pin "31") (pinfunction "PD6_/UART2_RX_31") (pintype "passive"))
    )
    (net (code "48") (name "/UART2_TX") (class "Default")
      (node (ref "P7") (pin "1") (pinfunction "1_1") (pintype "passive"))
      (node (ref "U6") (pin "30") (pinfunction "PD5_/UART2_TX_30") (pintype "passive"))
    )
    (net (code "49") (name "GND") (class "Default")
      (node (ref "C1") (pin "1") (pinfunction "1_1") (pintype "passive"))
      (node (ref "C10") (pin "1") (pinfunction "1_1") (pintype "passive"))
      (node (ref "C11") (pin "1") (pinfunction "1_1") (pintype "passive"))
      (node (ref "C14") (pin "2") (pinfunction "2_2") (pintype "passive"))
      (node (ref "C15") (pin "1") (pinfunction "1_1") (pintype "passive"))
      (node (ref "C16") (pin "1") (pinfunction "1_1") (pintype "passive"))
      (node (ref "C17") (pin "1") (pinfunction "1_1") (pintype "passive"))
      (node (ref "C18") (pin "2") (pinfunction "2_2") (pintype "passive"))
      (node (ref "C19") (pin "1") (pinfunction "1_1") (pintype "passive"))
      (node (ref "C2") (pin "1") (pinfunction "1_1") (pintype "passive"))
      (node (ref "C20") (pin "1") (pinfunction "1_1") (pintype "passive"))
      (node (ref "C3") (pin "1") (pinfunction "1_1") (pintype "passive"))
      (node (ref "C4") (pin "1") (pinfunction "1_1") (pintype "passive"))
      (node (ref "C5") (pin "1") (pinfunction "1_1") (pintype "passive"))
      (node (ref "C6") (pin "1") (pinfunction "1_1") (pintype "passive"))
      (node (ref "C7") (pin "1") (pinfunction "1_1") (pintype "passive"))
      (node (ref "C8") (pin "1") (pinfunction "1_1") (pintype "passive"))
      (node (ref "C9") (pin "2") (pinfunction "2_2") (pintype "passive"))
      (node (ref "N1") (pin "2") (pinfunction "2_2") (pintype "passive"))
      (node (ref "P1") (pin "2") (pinfunction "2_2") (pintype "passive"))
      (node (ref "P2") (pin "3") (pinfunction "3_3") (pintype "passive"))
      (node (ref "P3") (pin "2") (pinfunction "2_2") (pintype "passive"))
      (node (ref "P7") (pin "3") (pinfunction "3_3") (pintype "passive"))
      (node (ref "P8") (pin "2") (pinfunction "2_2") (pintype "passive"))
      (node (ref "P9") (pin "4") (pinfunction "4_4") (pintype "passive"))
      (node (ref "Q1") (pin "2") (pinfunction "E_2") (pintype "passive"))
      (node (ref "Q7") (pin "2") (pinfunction "E_2") (pintype "passive"))
      (node (ref "Q9") (pin "2") (pinfunction "E_2") (pintype "passive"))
      (node (ref "U1") (pin "7") (pinfunction "VSS_7") (pintype "passive"))
      (node (ref "U2") (pin "2") (pinfunction "GND_2") (pintype "passive"))
      (node (ref "U3") (pin "7") (pinfunction "GND_7") (pintype "power_in"))
      (node (ref "U6") (pin "10") (pinfunction "VSSA_10") (pintype "passive"))
      (node (ref "U6") (pin "4") (pinfunction "VSS_4") (pintype "passive"))
      (node (ref "U7") (pin "4") (pinfunction "V-_4") (pintype "power_in"))
      (node (ref "U7") (pin "5") (pinfunction "IN+_5") (pintype "input"))
    )
    (net (code "50") (name "Net-(C12-Pad2)") (class "Default")
      (node (ref "C12") (pin "2") (pinfunction "2_2") (pintype "passive"))
      (node (ref "R18") (pin "2") (pinfunction "2_2") (pintype "passive"))
    )
    (net (code "51") (name "Net-(C13-Pad2)") (class "Default")
      (node (ref "C13") (pin "2") (pinfunction "2_2") (pintype "passive"))
      (node (ref "R25") (pin "2") (pinfunction "2_2") (pintype "passive"))
    )
    (net (code "52") (name "Net-(D1-DP5{slash}6)") (class "Default")
      (node (ref "D1") (pin "8") (pinfunction "DP5/6_8") (pintype "passive"))
      (node (ref "R3") (pin "1") (pinfunction "1_1") (pintype "passive"))
    )
    (net (code "53") (name "Net-(D2-A)") (class "Default")
      (node (ref "D2") (pin "1") (pinfunction "A_1") (pintype "passive"))
      (node (ref "P3") (pin "1") (pinfunction "1_1") (pintype "passive"))
    )
    (net (code "54") (name "Net-(D5-A)") (class "Default")
      (node (ref "D5") (pin "1") (pinfunction "A_1") (pintype "passive"))
      (node (ref "R16") (pin "2") (pinfunction "2_2") (pintype "passive"))
    )
    (net (code "55") (name "Net-(D5-K)") (class "Default")
      (node (ref "D5") (pin "2") (pinfunction "K_2") (pintype "passive"))
      (node (ref "U4") (pin "1") (pinfunction "A_1") (pintype "passive"))
    )
    (net (code "56") (name "Net-(D8-K)") (class "Default")
      (node (ref "D8") (pin "2") (pinfunction "K_2") (pintype "passive"))
      (node (ref "R22") (pin "2") (pinfunction "2_2") (pintype "passive"))
    )
    (net (code "57") (name "Net-(D9-A)") (class "Default")
      (node (ref "D9") (pin "1") (pinfunction "A_1") (pintype "passive"))
      (node (ref "R24") (pin "2") (pinfunction "2_2") (pintype "passive"))
    )
    (net (code "58") (name "Net-(D9-K)") (class "Default")
      (node (ref "D9") (pin "2") (pinfunction "K_2") (pintype "passive"))
      (node (ref "U5") (pin "1") (pinfunction "A_1") (pintype "passive"))
    )
    (net (code "59") (name "Net-(K1-K)") (class "Default")
      (node (ref "K1") (pin "3") (pinfunction "K_3") (pintype "passive"))
      (node (ref "R13") (pin "2") (pinfunction "2_2") (pintype "passive"))
    )
    (net (code "60") (name "Net-(K2-K)") (class "Default")
      (node (ref "K2") (pin "3") (pinfunction "K_3") (pintype "passive"))
      (node (ref "R14") (pin "2") (pinfunction "2_2") (pintype "passive"))
    )
    (net (code "61") (name "Net-(K3-K)") (class "Default")
      (node (ref "K3") (pin "3") (pinfunction "K_3") (pintype "passive"))
      (node (ref "R17") (pin "2") (pinfunction "2_2") (pintype "passive"))
    )
    (net (code "62") (name "Net-(K4-K)") (class "Default")
      (node (ref "K4") (pin "3") (pinfunction "K_3") (pintype "passive"))
      (node (ref "R21") (pin "2") (pinfunction "2_2") (pintype "passive"))
    )
    (net (code "63") (name "Net-(Q1-B)") (class "Default")
      (node (ref "Q1") (pin "1") (pinfunction "B_1") (pintype "passive"))
      (node (ref "R8") (pin "2") (pinfunction "2_2") (pintype "passive"))
    )
    (net (code "64") (name "Net-(Q1-C)") (class "Default")
      (node (ref "LS1") (pin "2") (pinfunction "2_2") (pintype "passive"))
      (node (ref "Q1") (pin "3") (pinfunction "C_3") (pintype "passive"))
    )
    (net (code "65") (name "Net-(Q2-B)") (class "Default")
      (node (ref "Q2") (pin "1") (pinfunction "B_1") (pintype "passive"))
      (node (ref "R9") (pin "1") (pinfunction "1_1") (pintype "passive"))
    )
    (net (code "66") (name "Net-(Q2-C)") (class "Default")
      (node (ref "Q2") (pin "3") (pinfunction "C_3") (pintype "passive"))
      (node (ref "R4") (pin "1") (pinfunction "1_1") (pintype "passive"))
    )
    (net (code "67") (name "Net-(Q3-B)") (class "Default")
      (node (ref "Q3") (pin "1") (pinfunction "B_1") (pintype "passive"))
      (node (ref "R10") (pin "1") (pinfunction "1_1") (pintype "passive"))
    )
    (net (code "68") (name "Net-(Q3-C)") (class "Default")
      (node (ref "Q3") (pin "3") (pinfunction "C_3") (pintype "passive"))
      (node (ref "R5") (pin "1") (pinfunction "1_1") (pintype "passive"))
    )
    (net (code "69") (name "Net-(Q4-B)") (class "Default")
      (node (ref "Q4") (pin "1") (pinfunction "B_1") (pintype "passive"))
      (node (ref "R11") (pin "1") (pinfunction "1_1") (pintype "passive"))
    )
    (net (code "70") (name "Net-(Q4-C)") (class "Default")
      (node (ref "Q4") (pin "3") (pinfunction "C_3") (pintype "passive"))
      (node (ref "R6") (pin "1") (pinfunction "1_1") (pintype "passive"))
    )
    (net (code "71") (name "Net-(Q5-B)") (class "Default")
      (node (ref "Q5") (pin "1") (pinfunction "B_1") (pintype "passive"))
      (node (ref "R12") (pin "1") (pinfunction "1_1") (pintype "passive"))
    )
    (net (code "72") (name "Net-(Q5-C)") (class "Default")
      (node (ref "Q5") (pin "3") (pinfunction "C_3") (pintype "passive"))
      (node (ref "R7") (pin "1") (pinfunction "1_1") (pintype "passive"))
    )
    (net (code "73") (name "Net-(Q6-G)") (class "Default")
      (node (ref "Q6") (pin "3") (pinfunction "G_3") (pintype "passive"))
      (node (ref "R19") (pin "2") (pinfunction "2_2") (pintype "passive"))
      (node (ref "U4") (pin "4") (pinfunction "A/K_4") (pintype "passive"))
    )
    (net (code "74") (name "Net-(Q7-B)") (class "Default")
      (node (ref "Q7") (pin "1") (pinfunction "B_1") (pintype "passive"))
      (node (ref "R20") (pin "2") (pinfunction "2_2") (pintype "passive"))
    )
    (net (code "75") (name "Net-(Q7-C)") (class "Default")
      (node (ref "Q7") (pin "3") (pinfunction "C_3") (pintype "passive"))
      (node (ref "U4") (pin "2") (pinfunction "K_2") (pintype "passive"))
    )
    (net (code "76") (name "Net-(Q8-G)") (class "Default")
      (node (ref "Q8") (pin "3") (pinfunction "G_3") (pintype "passive"))
      (node (ref "R26") (pin "2") (pinfunction "2_2") (pintype "passive"))
      (node (ref "U5") (pin "4") (pinfunction "A/K_4") (pintype "passive"))
    )
    (net (code "77") (name "Net-(Q9-B)") (class "Default")
      (node (ref "Q9") (pin "1") (pinfunction "B_1") (pintype "passive"))
      (node (ref "R27") (pin "2") (pinfunction "2_2") (pintype "passive"))
    )
    (net (code "78") (name "Net-(Q9-C)") (class "Default")
      (node (ref "Q9") (pin "3") (pinfunction "C_3") (pintype "passive"))
      (node (ref "U5") (pin "2") (pinfunction "K_2") (pintype "passive"))
    )
    (net (code "79") (name "Net-(R15-Pad2)") (class "Default")
      (node (ref "R15") (pin "2") (pinfunction "2_2") (pintype "passive"))
      (node (ref "U4") (pin "6") (pinfunction "A/K_6") (pintype "passive"))
    )
    (net (code "80") (name "Net-(R23-Pad2)") (class "Default")
      (node (ref "R23") (pin "2") (pinfunction "2_2") (pintype "passive"))
      (node (ref "U5") (pin "6") (pinfunction "A/K_6") (pintype "passive"))
    )
    (net (code "81") (name "Net-(R29-BOT)") (class "Default")
      (node (ref "R29") (pin "2") (pinfunction "BOT_2") (pintype "passive"))
      (node (ref "U7") (pin "3") (pinfunction "IN+_3") (pintype "input"))
      (node (ref "U7") (pin "7") (pinfunction "OUT_7") (pintype "output"))
    )
    (net (code "82") (name "Net-(R29-TAP)") (class "Default")
      (node (ref "R28") (pin "1") (pinfunction "1_1") (pintype "passive"))
      (node (ref "R29") (pin "1") (pinfunction "TOP_1") (pintype "passive"))
      (node (ref "R29") (pin "3") (pinfunction "TAP_3") (pintype "passive"))
    )
    (net (code "83") (name "Net-(U1-VDD)") (class "Default")
      (node (ref "C2") (pin "2") (pinfunction "2_2") (pintype "passive"))
      (node (ref "L1") (pin "2") (pinfunction "2_2") (pintype "passive"))
      (node (ref "U1") (pin "8") (pinfunction "VDD_8") (pintype "passive"))
    )
    (net (code "84") (name "Net-(U6-PA1{slash}OSCIN)") (class "Default")
      (node (ref "C15") (pin "2") (pinfunction "2_2") (pintype "passive"))
      (node (ref "U6") (pin "2") (pinfunction "PA1/OSCIN_2") (pintype "passive"))
      (node (ref "Y1") (pin "1") (pinfunction "OSC1_1") (pintype "passive"))
    )
    (net (code "85") (name "Net-(U6-PA2{slash}OSCOUT)") (class "Default")
      (node (ref "C16") (pin "2") (pinfunction "2_2") (pintype "passive"))
      (node (ref "U6") (pin "3") (pinfunction "PA2/OSCOUT_3") (pintype "passive"))
      (node (ref "Y1") (pin "2") (pinfunction "OSC2_2") (pintype "passive"))
    )
    (net (code "86") (name "Net-(U6-VCAP)") (class "Default")
      (node (ref "C17") (pin "2") (pinfunction "2_2") (pintype "passive"))
      (node (ref "U6") (pin "5") (pinfunction "VCAP_5") (pintype "passive"))
    )
    (net (code "87") (name "Net-(U7B-IN-)") (class "Default")
      (node (ref "R28") (pin "2") (pinfunction "2_2") (pintype "passive"))
      (node (ref "R30") (pin "1") (pinfunction "1_1") (pintype "passive"))
      (node (ref "U7") (pin "6") (pinfunction "IN-_6") (pintype "input"))
    )
    (net (code "88") (name "unconnected-(M1-PadS)") (class "Default")
      (node (ref "M1") (pin "S") (pinfunction "S_S") (pintype "passive"))
    )
    (net (code "89") (name "unconnected-(M2-PadS)") (class "Default")
      (node (ref "M2") (pin "S") (pinfunction "S_S") (pintype "passive"))
    )
    (net (code "90") (name "unconnected-(M3-PadS)") (class "Default")
      (node (ref "M3") (pin "S") (pinfunction "S_S") (pintype "passive"))
    )
    (net (code "91") (name "unconnected-(M4-PadS)") (class "Default")
      (node (ref "M4") (pin "S") (pinfunction "S_S") (pintype "passive"))
    )
    (net (code "92") (name "unconnected-(U4-NC-Pad3)") (class "Default")
      (node (ref "U4") (pin "3") (pinfunction "NC_3") (pintype "passive"))
    )
    (net (code "93") (name "unconnected-(U4-NC-Pad5)") (class "Default")
      (node (ref "U4") (pin "5") (pinfunction "NC_5") (pintype "passive"))
    )
    (net (code "94") (name "unconnected-(U5-NC-Pad3)") (class "Default")
      (node (ref "U5") (pin "3") (pinfunction "NC_3") (pintype "passive"))
    )
    (net (code "95") (name "unconnected-(U5-NC-Pad5)") (class "Default")
      (node (ref "U5") (pin "5") (pinfunction "NC_5") (pintype "passive"))
    )
    (net (code "96") (name "unconnected-(U7B-V+-Pad8)") (class "Default")
      (node (ref "U7") (pin "8") (pinfunction "V+_8") (pintype "power_in"))
    )
    (net (code "97") (name "unconnected-(U7B-V--Pad4)") (class "Default")
      (node (ref "U7") (pin "4") (pinfunction "V-_4") (pintype "power_in"))
    )
  )
)
